# OpenPLCv0_2_0_SerialInterface.net
KiCad netlist of a schematic drawn in Altium Designer
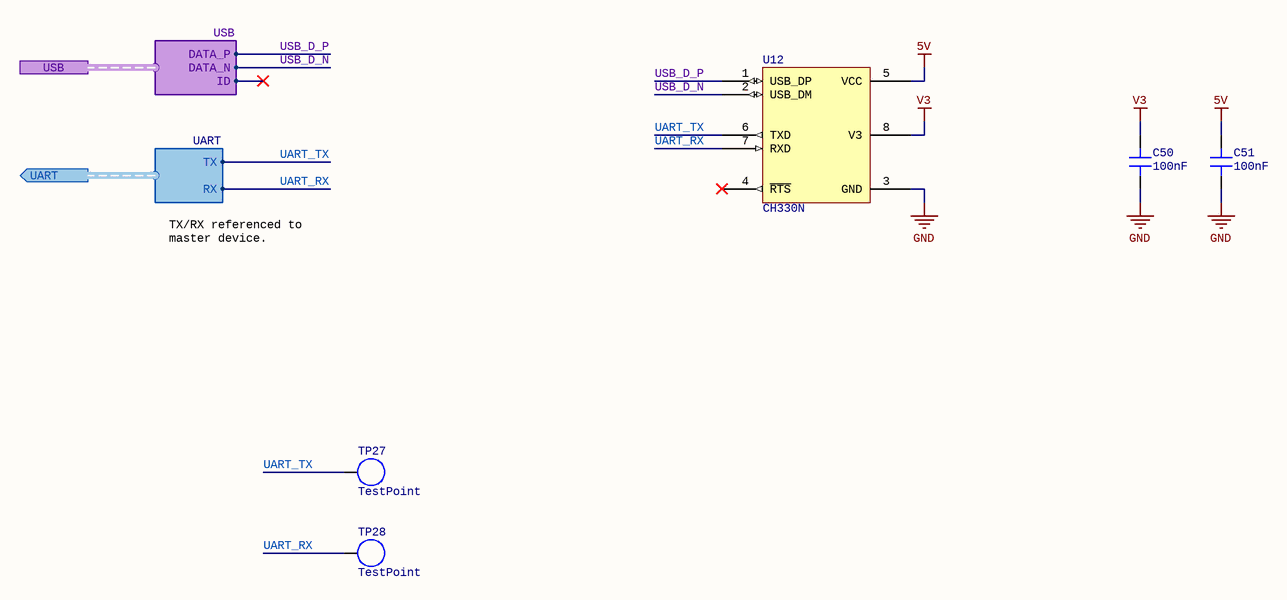
[diagram p0: OpenPLCv0.2.0_SerialInterface.SchDoc]

(export (version "E")
  (design (tool "Eeschema 10.0.6"))
  (components
    (comp (ref "C50")
      (value "CC0402KRX5R6BB104")
      (footprint "SMD_CAP_0402(1005)_N")
      (description "100nF ±10% 10V X5R 0402 Multilayer Ceramic Capacitors MLCC - SMD/SMT RoHS")
      (fields (field (name "TOLERANCE") "10%") (field (name "CAPACITANCE") "100nF"))
      (libsource (lib "BrauV2_Capacitor") (part "100nF 0402 10V 10%"))
    )
    (comp (ref "C51")
      (value "CC0402KRX5R6BB104")
      (footprint "SMD_CAP_0402(1005)_N")
      (description "100nF ±10% 10V X5R 0402 Multilayer Ceramic Capacitors MLCC - SMD/SMT RoHS")
      (fields (field (name "TOLERANCE") "10%") (field (name "CAPACITANCE") "100nF"))
      (libsource (lib "BrauV2_Capacitor") (part "100nF 0402 10V 10%"))
    )
    (comp (ref "TP27")
      (value "TestPoint")
      (footprint "Pad")
      (libsource (lib "OpenPLCv0.2.0_Misc") (part "Test point"))
    )
    (comp (ref "TP28")
      (value "TestPoint")
      (footprint "Pad")
      (libsource (lib "OpenPLCv0.2.0_Misc") (part "Test point"))
    )
    (comp (ref "U12")
      (value "CH330N")
      (footprint "SOIC-8-3.9mm")
      (description "Transceiver USB 2.0 2Mbps SOP-8_150mil USB ICs RoHS")
      (libsource (lib "BrauV2_IC") (part "CH330N"))
    )
  )
  (nets
    (net (code "3") (name "/UART_RX") (class "Default")
      (node (ref "TP28") (pin "1") (pinfunction "1_1") (pintype "passive"))
      (node (ref "U12") (pin "7") (pinfunction "RXD_7") (pintype "input"))
    )
    (net (code "4") (name "/UART_TX") (class "Default")
      (node (ref "TP27") (pin "1") (pinfunction "1_1") (pintype "passive"))
      (node (ref "U12") (pin "6") (pinfunction "TXD_6") (pintype "output"))
    )
    (net (code "5") (name "/USB_D_N") (class "Default")
      (node (ref "U12") (pin "2") (pinfunction "USB_DM_2") (pintype "bidirectional"))
    )
    (net (code "6") (name "/USB_D_P") (class "Default")
      (node (ref "U12") (pin "1") (pinfunction "USB_DP_1") (pintype "bidirectional"))
    )
    (net (code "9") (name "5V") (class "Default")
      (node (ref "C51") (pin "2") (pinfunction "2_2") (pintype "passive"))
      (node (ref "U12") (pin "5") (pinfunction "VCC_5") (pintype "power_in"))
    )
    (net (code "10") (name "GND") (class "Default")
      (node (ref "C50") (pin "1") (pinfunction "1_1") (pintype "passive"))
      (node (ref "C51") (pin "1") (pinfunction "1_1") (pintype "passive"))
      (node (ref "U12") (pin "3") (pinfunction "GND_3") (pintype "power_in"))
    )
    (net (code "11") (name "V3") (class "Default")
      (node (ref "C50") (pin "2") (pinfunction "2_2") (pintype "passive"))
      (node (ref "U12") (pin "8") (pinfunction "V3_8") (pintype "power_in"))
    )
    (net (code "12") (name "unconnected-(U12-~{RTS}-Pad4)") (class "Default")
      (node (ref "U12") (pin "4") (pinfunction "~{RTS}_4") (pintype "output+no_connect"))
    )
  )
)
